# FY_-_OPTO_BOARD_2_MISC.net
KiCad netlist of a schematic drawn in EAGLE
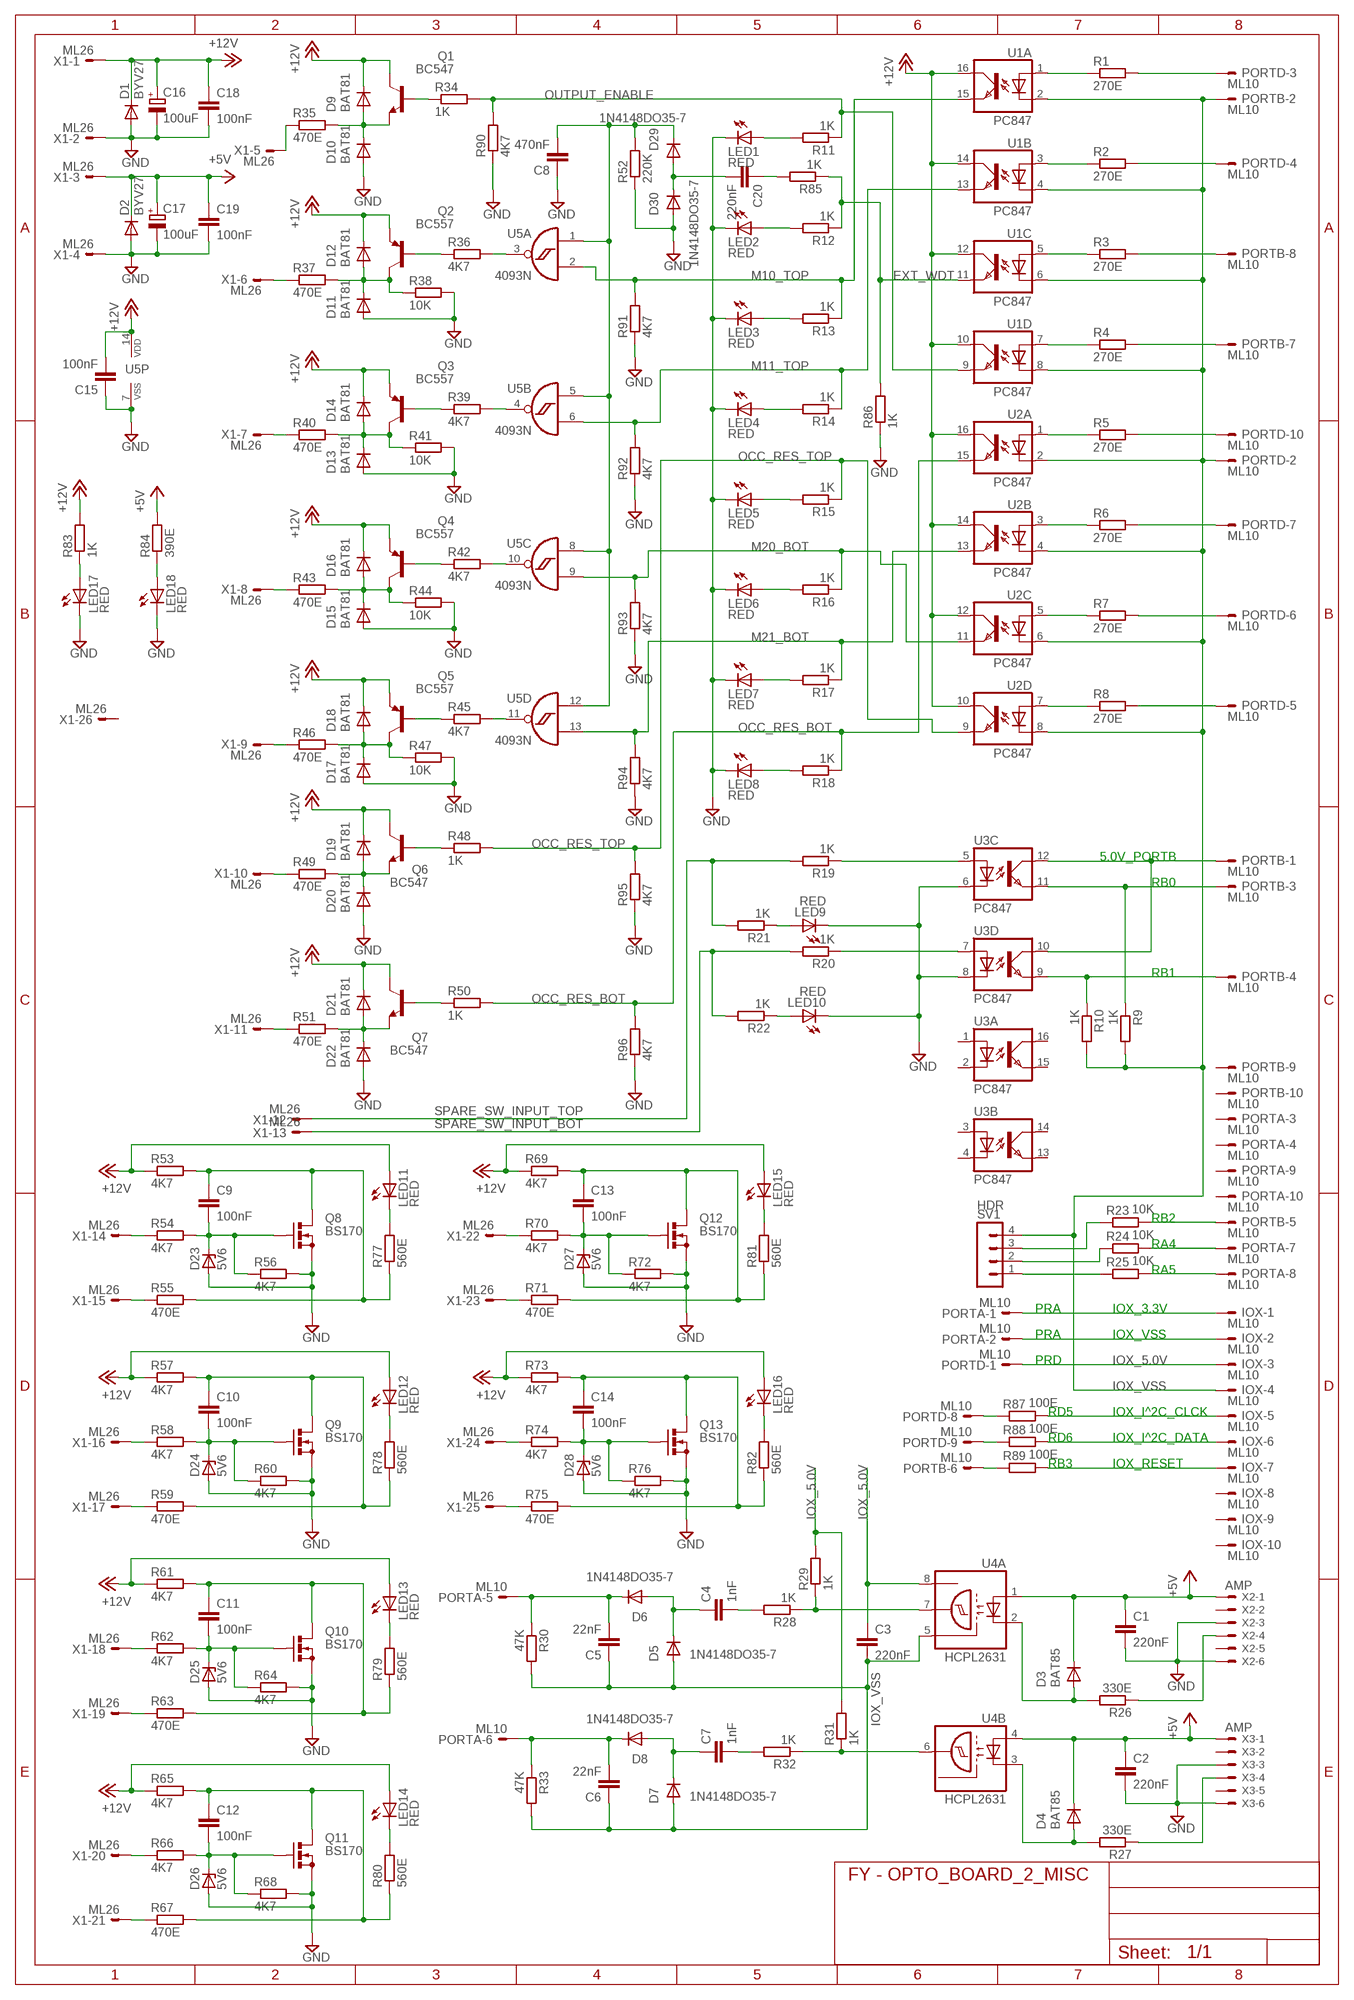
[diagram p0: schematic, sheet 1]

(export (version "E")
  (design (tool "Eeschema 10.0.6"))
  (components
    (comp (ref "C1")
      (value "220nF")
      (footprint "eagle-import:C050-025X075")
      (libsource (lib "eagle-import") (part "C-EU050-025X075"))
    )
    (comp (ref "C2")
      (value "220nF")
      (footprint "eagle-import:C050-025X075")
      (libsource (lib "eagle-import") (part "C-EU050-025X075"))
    )
    (comp (ref "C3")
      (value "220nF")
      (footprint "eagle-import:C050-025X075")
      (libsource (lib "eagle-import") (part "C-EU050-025X075"))
    )
    (comp (ref "C4")
      (value "1nF")
      (footprint "eagle-import:C050-025X075")
      (libsource (lib "eagle-import") (part "C-EU050-025X075"))
    )
    (comp (ref "C5")
      (value "22nF")
      (footprint "eagle-import:C050-025X075")
      (libsource (lib "eagle-import") (part "C-EU050-025X075"))
    )
    (comp (ref "C6")
      (value "22nF")
      (footprint "eagle-import:C050-025X075")
      (libsource (lib "eagle-import") (part "C-EU050-025X075"))
    )
    (comp (ref "C7")
      (value "1nF")
      (footprint "eagle-import:C050-025X075")
      (libsource (lib "eagle-import") (part "C-EU050-025X075"))
    )
    (comp (ref "C8")
      (value "470nF")
      (footprint "eagle-import:C050-025X075")
      (libsource (lib "eagle-import") (part "C-EU050-025X075"))
    )
    (comp (ref "C9")
      (value "100nF")
      (footprint "eagle-import:C050-025X075")
      (libsource (lib "eagle-import") (part "C-EU050-025X075"))
    )
    (comp (ref "C10")
      (value "100nF")
      (footprint "eagle-import:C050-025X075")
      (libsource (lib "eagle-import") (part "C-EU050-025X075"))
    )
    (comp (ref "C11")
      (value "100nF")
      (footprint "eagle-import:C050-025X075")
      (libsource (lib "eagle-import") (part "C-EU050-025X075"))
    )
    (comp (ref "C12")
      (value "100nF")
      (footprint "eagle-import:C050-025X075")
      (libsource (lib "eagle-import") (part "C-EU050-025X075"))
    )
    (comp (ref "C13")
      (value "100nF")
      (footprint "eagle-import:C050-025X075")
      (libsource (lib "eagle-import") (part "C-EU050-025X075"))
    )
    (comp (ref "C14")
      (value "100nF")
      (footprint "eagle-import:C050-025X075")
      (libsource (lib "eagle-import") (part "C-EU050-025X075"))
    )
    (comp (ref "C15")
      (value "100nF")
      (footprint "eagle-import:C050-025X075")
      (libsource (lib "eagle-import") (part "C-EU050-025X075"))
    )
    (comp (ref "C16")
      (value "100uF")
      (footprint "eagle-import:E5-8,5")
      (libsource (lib "eagle-import") (part "CPOL-EUE5-8.5"))
    )
    (comp (ref "C17")
      (value "100uF")
      (footprint "eagle-import:E5-8,5")
      (libsource (lib "eagle-import") (part "CPOL-EUE5-8.5"))
    )
    (comp (ref "C18")
      (value "100nF")
      (footprint "eagle-import:C050-025X075")
      (libsource (lib "eagle-import") (part "C-EU050-025X075"))
    )
    (comp (ref "C19")
      (value "100nF")
      (footprint "eagle-import:C050-025X075")
      (libsource (lib "eagle-import") (part "C-EU050-025X075"))
    )
    (comp (ref "C20")
      (value "220nF")
      (footprint "eagle-import:C050-025X075")
      (libsource (lib "eagle-import") (part "C-EU050-025X075"))
    )
    (comp (ref "D1")
      (value "BYV27")
      (footprint "eagle-import:SOD57-10")
      (libsource (lib "eagle-import") (part "BYV27"))
    )
    (comp (ref "D2")
      (value "BYV27")
      (footprint "eagle-import:SOD57-10")
      (libsource (lib "eagle-import") (part "BYV27"))
    )
    (comp (ref "D3")
      (value "BAT85")
      (footprint "eagle-import:DO34-7")
      (libsource (lib "eagle-import") (part "BAT81"))
    )
    (comp (ref "D4")
      (value "BAT85")
      (footprint "eagle-import:DO34-7")
      (libsource (lib "eagle-import") (part "BAT81"))
    )
    (comp (ref "D5")
      (value "1N4148DO35-7")
      (footprint "eagle-import:DO35-7")
      (libsource (lib "eagle-import") (part "1N4148DO35-7"))
    )
    (comp (ref "D6")
      (value "1N4148DO35-7")
      (footprint "eagle-import:DO35-7")
      (libsource (lib "eagle-import") (part "1N4148DO35-7"))
    )
    (comp (ref "D7")
      (value "1N4148DO35-7")
      (footprint "eagle-import:DO35-7")
      (libsource (lib "eagle-import") (part "1N4148DO35-7"))
    )
    (comp (ref "D8")
      (value "1N4148DO35-7")
      (footprint "eagle-import:DO35-7")
      (libsource (lib "eagle-import") (part "1N4148DO35-7"))
    )
    (comp (ref "D9")
      (value "BAT81")
      (footprint "eagle-import:DO34-7")
      (libsource (lib "eagle-import") (part "BAT81"))
    )
    (comp (ref "D10")
      (value "BAT81")
      (footprint "eagle-import:DO34-7")
      (libsource (lib "eagle-import") (part "BAT81"))
    )
    (comp (ref "D11")
      (value "BAT81")
      (footprint "eagle-import:DO34-7")
      (libsource (lib "eagle-import") (part "BAT81"))
    )
    (comp (ref "D12")
      (value "BAT81")
      (footprint "eagle-import:DO34-7")
      (libsource (lib "eagle-import") (part "BAT81"))
    )
    (comp (ref "D13")
      (value "BAT81")
      (footprint "eagle-import:DO34-7")
      (libsource (lib "eagle-import") (part "BAT81"))
    )
    (comp (ref "D14")
      (value "BAT81")
      (footprint "eagle-import:DO34-7")
      (libsource (lib "eagle-import") (part "BAT81"))
    )
    (comp (ref "D15")
      (value "BAT81")
      (footprint "eagle-import:DO34-7")
      (libsource (lib "eagle-import") (part "BAT81"))
    )
    (comp (ref "D16")
      (value "BAT81")
      (footprint "eagle-import:DO34-7")
      (libsource (lib "eagle-import") (part "BAT81"))
    )
    (comp (ref "D17")
      (value "BAT81")
      (footprint "eagle-import:DO34-7")
      (libsource (lib "eagle-import") (part "BAT81"))
    )
    (comp (ref "D18")
      (value "BAT81")
      (footprint "eagle-import:DO34-7")
      (libsource (lib "eagle-import") (part "BAT81"))
    )
    (comp (ref "D19")
      (value "BAT81")
      (footprint "eagle-import:DO34-7")
      (libsource (lib "eagle-import") (part "BAT81"))
    )
    (comp (ref "D20")
      (value "BAT81")
      (footprint "eagle-import:DO34-7")
      (libsource (lib "eagle-import") (part "BAT81"))
    )
    (comp (ref "D21")
      (value "BAT81")
      (footprint "eagle-import:DO34-7")
      (libsource (lib "eagle-import") (part "BAT81"))
    )
    (comp (ref "D22")
      (value "BAT81")
      (footprint "eagle-import:DO34-7")
      (libsource (lib "eagle-import") (part "BAT81"))
    )
    (comp (ref "D23")
      (value "5V6")
      (footprint "eagle-import:DO34Z7")
      (libsource (lib "eagle-import") (part "ZENER-DIODEDO34-7"))
    )
    (comp (ref "D24")
      (value "5V6")
      (footprint "eagle-import:DO34Z7")
      (libsource (lib "eagle-import") (part "ZENER-DIODEDO34-7"))
    )
    (comp (ref "D25")
      (value "5V6")
      (footprint "eagle-import:DO34Z7")
      (libsource (lib "eagle-import") (part "ZENER-DIODEDO34-7"))
    )
    (comp (ref "D26")
      (value "5V6")
      (footprint "eagle-import:DO34Z7")
      (libsource (lib "eagle-import") (part "ZENER-DIODEDO34-7"))
    )
    (comp (ref "D27")
      (value "5V6")
      (footprint "eagle-import:DO34Z7")
      (libsource (lib "eagle-import") (part "ZENER-DIODEDO34-7"))
    )
    (comp (ref "D28")
      (value "5V6")
      (footprint "eagle-import:DO34Z7")
      (libsource (lib "eagle-import") (part "ZENER-DIODEDO34-7"))
    )
    (comp (ref "D29")
      (value "1N4148DO35-7")
      (footprint "eagle-import:DO35-7")
      (libsource (lib "eagle-import") (part "1N4148DO35-7"))
    )
    (comp (ref "D30")
      (value "1N4148DO35-7")
      (footprint "eagle-import:DO35-7")
      (libsource (lib "eagle-import") (part "1N4148DO35-7"))
    )
    (comp (ref "IOX")
      (value "ML10")
      (footprint "eagle-import:ML10")
      (libsource (lib "eagle-import") (part "ML10?E"))
    )
    (comp (ref "LED1")
      (value "RED")
      (footprint "eagle-import:LED3MM")
      (libsource (lib "eagle-import") (part "LED3MM"))
    )
    (comp (ref "LED2")
      (value "RED")
      (footprint "eagle-import:LED3MM")
      (libsource (lib "eagle-import") (part "LED3MM"))
    )
    (comp (ref "LED3")
      (value "RED")
      (footprint "eagle-import:LED3MM")
      (libsource (lib "eagle-import") (part "LED3MM"))
    )
    (comp (ref "LED4")
      (value "RED")
      (footprint "eagle-import:LED3MM")
      (libsource (lib "eagle-import") (part "LED3MM"))
    )
    (comp (ref "LED5")
      (value "RED")
      (footprint "eagle-import:LED3MM")
      (libsource (lib "eagle-import") (part "LED3MM"))
    )
    (comp (ref "LED6")
      (value "RED")
      (footprint "eagle-import:LED3MM")
      (libsource (lib "eagle-import") (part "LED3MM"))
    )
    (comp (ref "LED7")
      (value "RED")
      (footprint "eagle-import:LED3MM")
      (libsource (lib "eagle-import") (part "LED3MM"))
    )
    (comp (ref "LED8")
      (value "RED")
      (footprint "eagle-import:LED3MM")
      (libsource (lib "eagle-import") (part "LED3MM"))
    )
    (comp (ref "LED9")
      (value "RED")
      (footprint "eagle-import:LED3MM")
      (libsource (lib "eagle-import") (part "LED3MM"))
    )
    (comp (ref "LED10")
      (value "RED")
      (footprint "eagle-import:LED3MM")
      (libsource (lib "eagle-import") (part "LED3MM"))
    )
    (comp (ref "LED11")
      (value "RED")
      (footprint "eagle-import:LED3MM")
      (libsource (lib "eagle-import") (part "LED3MM"))
    )
    (comp (ref "LED12")
      (value "RED")
      (footprint "eagle-import:LED3MM")
      (libsource (lib "eagle-import") (part "LED3MM"))
    )
    (comp (ref "LED13")
      (value "RED")
      (footprint "eagle-import:LED3MM")
      (libsource (lib "eagle-import") (part "LED3MM"))
    )
    (comp (ref "LED14")
      (value "RED")
      (footprint "eagle-import:LED3MM")
      (libsource (lib "eagle-import") (part "LED3MM"))
    )
    (comp (ref "LED15")
      (value "RED")
      (footprint "eagle-import:LED3MM")
      (libsource (lib "eagle-import") (part "LED3MM"))
    )
    (comp (ref "LED16")
      (value "RED")
      (footprint "eagle-import:LED3MM")
      (libsource (lib "eagle-import") (part "LED3MM"))
    )
    (comp (ref "LED17")
      (value "RED")
      (footprint "eagle-import:LED3MM")
      (libsource (lib "eagle-import") (part "LED3MM"))
    )
    (comp (ref "LED18")
      (value "RED")
      (footprint "eagle-import:LED3MM")
      (libsource (lib "eagle-import") (part "LED3MM"))
    )
    (comp (ref "PORTA")
      (value "ML10")
      (footprint "eagle-import:ML10")
      (libsource (lib "eagle-import") (part "ML10?E"))
    )
    (comp (ref "PORTB")
      (value "ML10")
      (footprint "eagle-import:ML10")
      (libsource (lib "eagle-import") (part "ML10?E"))
    )
    (comp (ref "PORTD")
      (value "ML10")
      (footprint "eagle-import:ML10")
      (libsource (lib "eagle-import") (part "ML10?E"))
    )
    (comp (ref "Q1")
      (value "BC547")
      (footprint "eagle-import:TO92")
      (libsource (lib "eagle-import") (part "BC547"))
    )
    (comp (ref "Q2")
      (value "BC557")
      (footprint "eagle-import:TO92")
      (libsource (lib "eagle-import") (part "BC557"))
    )
    (comp (ref "Q3")
      (value "BC557")
      (footprint "eagle-import:TO92")
      (libsource (lib "eagle-import") (part "BC557"))
    )
    (comp (ref "Q4")
      (value "BC557")
      (footprint "eagle-import:TO92")
      (libsource (lib "eagle-import") (part "BC557"))
    )
    (comp (ref "Q5")
      (value "BC557")
      (footprint "eagle-import:TO92")
      (libsource (lib "eagle-import") (part "BC557"))
    )
    (comp (ref "Q6")
      (value "BC547")
      (footprint "eagle-import:TO92")
      (libsource (lib "eagle-import") (part "BC547"))
    )
    (comp (ref "Q7")
      (value "BC547")
      (footprint "eagle-import:TO92")
      (libsource (lib "eagle-import") (part "BC547"))
    )
    (comp (ref "Q8")
      (value "BS170")
      (footprint "eagle-import:SOT54E")
      (libsource (lib "eagle-import") (part "BS170"))
    )
    (comp (ref "Q9")
      (value "BS170")
      (footprint "eagle-import:SOT54E")
      (libsource (lib "eagle-import") (part "BS170"))
    )
    (comp (ref "Q10")
      (value "BS170")
      (footprint "eagle-import:SOT54E")
      (libsource (lib "eagle-import") (part "BS170"))
    )
    (comp (ref "Q11")
      (value "BS170")
      (footprint "eagle-import:SOT54E")
      (libsource (lib "eagle-import") (part "BS170"))
    )
    (comp (ref "Q12")
      (value "BS170")
      (footprint "eagle-import:SOT54E")
      (libsource (lib "eagle-import") (part "BS170"))
    )
    (comp (ref "Q13")
      (value "BS170")
      (footprint "eagle-import:SOT54E")
      (libsource (lib "eagle-import") (part "BS170"))
    )
    (comp (ref "R1")
      (value "270E")
      (footprint "eagle-import:0207_10")
      (libsource (lib "eagle-import") (part "R-EU_0207/10"))
    )
    (comp (ref "R2")
      (value "270E")
      (footprint "eagle-import:0207_10")
      (libsource (lib "eagle-import") (part "R-EU_0207/10"))
    )
    (comp (ref "R3")
      (value "270E")
      (footprint "eagle-import:0207_10")
      (libsource (lib "eagle-import") (part "R-EU_0207/10"))
    )
    (comp (ref "R4")
      (value "270E")
      (footprint "eagle-import:0207_10")
      (libsource (lib "eagle-import") (part "R-EU_0207/10"))
    )
    (comp (ref "R5")
      (value "270E")
      (footprint "eagle-import:0207_10")
      (libsource (lib "eagle-import") (part "R-EU_0207/10"))
    )
    (comp (ref "R6")
      (value "270E")
      (footprint "eagle-import:0207_10")
      (libsource (lib "eagle-import") (part "R-EU_0207/10"))
    )
    (comp (ref "R7")
      (value "270E")
      (footprint "eagle-import:0207_10")
      (libsource (lib "eagle-import") (part "R-EU_0207/10"))
    )
    (comp (ref "R8")
      (value "270E")
      (footprint "eagle-import:0207_10")
      (libsource (lib "eagle-import") (part "R-EU_0207/10"))
    )
    (comp (ref "R9")
      (value "1K")
      (footprint "eagle-import:0207_10")
      (libsource (lib "eagle-import") (part "R-EU_0207/10"))
    )
    (comp (ref "R10")
      (value "1K")
      (footprint "eagle-import:0207_10")
      (libsource (lib "eagle-import") (part "R-EU_0207/10"))
    )
    (comp (ref "R11")
      (value "1K")
      (footprint "eagle-import:0207_10")
      (libsource (lib "eagle-import") (part "R-EU_0207/10"))
    )
    (comp (ref "R12")
      (value "1K")
      (footprint "eagle-import:0207_10")
      (libsource (lib "eagle-import") (part "R-EU_0207/10"))
    )
    (comp (ref "R13")
      (value "1K")
      (footprint "eagle-import:0207_10")
      (libsource (lib "eagle-import") (part "R-EU_0207/10"))
    )
    (comp (ref "R14")
      (value "1K")
      (footprint "eagle-import:0207_10")
      (libsource (lib "eagle-import") (part "R-EU_0207/10"))
    )
    (comp (ref "R15")
      (value "1K")
      (footprint "eagle-import:0207_10")
      (libsource (lib "eagle-import") (part "R-EU_0207/10"))
    )
    (comp (ref "R16")
      (value "1K")
      (footprint "eagle-import:0207_10")
      (libsource (lib "eagle-import") (part "R-EU_0207/10"))
    )
    (comp (ref "R17")
      (value "1K")
      (footprint "eagle-import:0207_10")
      (libsource (lib "eagle-import") (part "R-EU_0207/10"))
    )
    (comp (ref "R18")
      (value "1K")
      (footprint "eagle-import:0207_10")
      (libsource (lib "eagle-import") (part "R-EU_0207/10"))
    )
    (comp (ref "R19")
      (value "1K")
      (footprint "eagle-import:0207_10")
      (libsource (lib "eagle-import") (part "R-EU_0207/10"))
    )
    (comp (ref "R20")
      (value "1K")
      (footprint "eagle-import:0207_10")
      (libsource (lib "eagle-import") (part "R-EU_0207/10"))
    )
    (comp (ref "R21")
      (value "1K")
      (footprint "eagle-import:0207_10")
      (libsource (lib "eagle-import") (part "R-EU_0207/10"))
    )
    (comp (ref "R22")
      (value "1K")
      (footprint "eagle-import:0207_10")
      (libsource (lib "eagle-import") (part "R-EU_0207/10"))
    )
    (comp (ref "R23")
      (value "10K")
      (footprint "eagle-import:0207_10")
      (libsource (lib "eagle-import") (part "R-EU_0207/10"))
    )
    (comp (ref "R24")
      (value "10K")
      (footprint "eagle-import:0207_10")
      (libsource (lib "eagle-import") (part "R-EU_0207/10"))
    )
    (comp (ref "R25")
      (value "10K")
      (footprint "eagle-import:0207_10")
      (libsource (lib "eagle-import") (part "R-EU_0207/10"))
    )
    (comp (ref "R26")
      (value "330E")
      (footprint "eagle-import:0207_10")
      (libsource (lib "eagle-import") (part "R-EU_0207/10"))
    )
    (comp (ref "R27")
      (value "330E")
      (footprint "eagle-import:0207_10")
      (libsource (lib "eagle-import") (part "R-EU_0207/10"))
    )
    (comp (ref "R28")
      (value "1K")
      (footprint "eagle-import:0207_10")
      (libsource (lib "eagle-import") (part "R-EU_0207/10"))
    )
    (comp (ref "R29")
      (value "1K")
      (footprint "eagle-import:0207_10")
      (libsource (lib "eagle-import") (part "R-EU_0207/10"))
    )
    (comp (ref "R30")
      (value "47K")
      (footprint "eagle-import:0207_10")
      (libsource (lib "eagle-import") (part "R-EU_0207/10"))
    )
    (comp (ref "R31")
      (value "1K")
      (footprint "eagle-import:0207_10")
      (libsource (lib "eagle-import") (part "R-EU_0207/10"))
    )
    (comp (ref "R32")
      (value "1K")
      (footprint "eagle-import:0207_10")
      (libsource (lib "eagle-import") (part "R-EU_0207/10"))
    )
    (comp (ref "R33")
      (value "47K")
      (footprint "eagle-import:0207_10")
      (libsource (lib "eagle-import") (part "R-EU_0207/10"))
    )
    (comp (ref "R34")
      (value "1K")
      (footprint "eagle-import:0207_10")
      (libsource (lib "eagle-import") (part "R-EU_0207/10"))
    )
    (comp (ref "R35")
      (value "470E")
      (footprint "eagle-import:0207_10")
      (libsource (lib "eagle-import") (part "R-EU_0207/10"))
    )
    (comp (ref "R36")
      (value "4K7")
      (footprint "eagle-import:0207_10")
      (libsource (lib "eagle-import") (part "R-EU_0207/10"))
    )
    (comp (ref "R37")
      (value "470E")
      (footprint "eagle-import:0207_10")
      (libsource (lib "eagle-import") (part "R-EU_0207/10"))
    )
    (comp (ref "R38")
      (value "10K")
      (footprint "eagle-import:0207_10")
      (libsource (lib "eagle-import") (part "R-EU_0207/10"))
    )
    (comp (ref "R39")
      (value "4K7")
      (footprint "eagle-import:0207_10")
      (libsource (lib "eagle-import") (part "R-EU_0207/10"))
    )
    (comp (ref "R40")
      (value "470E")
      (footprint "eagle-import:0207_10")
      (libsource (lib "eagle-import") (part "R-EU_0207/10"))
    )
    (comp (ref "R41")
      (value "10K")
      (footprint "eagle-import:0207_10")
      (libsource (lib "eagle-import") (part "R-EU_0207/10"))
    )
    (comp (ref "R42")
      (value "4K7")
      (footprint "eagle-import:0207_10")
      (libsource (lib "eagle-import") (part "R-EU_0207/10"))
    )
    (comp (ref "R43")
      (value "470E")
      (footprint "eagle-import:0207_10")
      (libsource (lib "eagle-import") (part "R-EU_0207/10"))
    )
    (comp (ref "R44")
      (value "10K")
      (footprint "eagle-import:0207_10")
      (libsource (lib "eagle-import") (part "R-EU_0207/10"))
    )
    (comp (ref "R45")
      (value "4K7")
      (footprint "eagle-import:0207_10")
      (libsource (lib "eagle-import") (part "R-EU_0207/10"))
    )
    (comp (ref "R46")
      (value "470E")
      (footprint "eagle-import:0207_10")
      (libsource (lib "eagle-import") (part "R-EU_0207/10"))
    )
    (comp (ref "R47")
      (value "10K")
      (footprint "eagle-import:0207_10")
      (libsource (lib "eagle-import") (part "R-EU_0207/10"))
    )
    (comp (ref "R48")
      (value "1K")
      (footprint "eagle-import:0207_10")
      (libsource (lib "eagle-import") (part "R-EU_0207/10"))
    )
    (comp (ref "R49")
      (value "470E")
      (footprint "eagle-import:0207_10")
      (libsource (lib "eagle-import") (part "R-EU_0207/10"))
    )
    (comp (ref "R50")
      (value "1K")
      (footprint "eagle-import:0207_10")
      (libsource (lib "eagle-import") (part "R-EU_0207/10"))
    )
    (comp (ref "R51")
      (value "470E")
      (footprint "eagle-import:0207_10")
      (libsource (lib "eagle-import") (part "R-EU_0207/10"))
    )
    (comp (ref "R52")
      (value "220K")
      (footprint "eagle-import:0207_10")
      (libsource (lib "eagle-import") (part "R-EU_0207/10"))
    )
    (comp (ref "R53")
      (value "4K7")
      (footprint "eagle-import:0207_10")
      (libsource (lib "eagle-import") (part "R-EU_0207/10"))
    )
    (comp (ref "R54")
      (value "4K7")
      (footprint "eagle-import:0207_10")
      (libsource (lib "eagle-import") (part "R-EU_0207/10"))
    )
    (comp (ref "R55")
      (value "470E")
      (footprint "eagle-import:0207_10")
      (libsource (lib "eagle-import") (part "R-EU_0207/10"))
    )
    (comp (ref "R56")
      (value "4K7")
      (footprint "eagle-import:0207_10")
      (libsource (lib "eagle-import") (part "R-EU_0207/10"))
    )
    (comp (ref "R57")
      (value "4K7")
      (footprint "eagle-import:0207_10")
      (libsource (lib "eagle-import") (part "R-EU_0207/10"))
    )
    (comp (ref "R58")
      (value "4K7")
      (footprint "eagle-import:0207_10")
      (libsource (lib "eagle-import") (part "R-EU_0207/10"))
    )
    (comp (ref "R59")
      (value "470E")
      (footprint "eagle-import:0207_10")
      (libsource (lib "eagle-import") (part "R-EU_0207/10"))
    )
    (comp (ref "R60")
      (value "4K7")
      (footprint "eagle-import:0207_10")
      (libsource (lib "eagle-import") (part "R-EU_0207/10"))
    )
    (comp (ref "R61")
      (value "4K7")
      (footprint "eagle-import:0207_10")
      (libsource (lib "eagle-import") (part "R-EU_0207/10"))
    )
    (comp (ref "R62")
      (value "4K7")
      (footprint "eagle-import:0207_10")
      (libsource (lib "eagle-import") (part "R-EU_0207/10"))
    )
    (comp (ref "R63")
      (value "470E")
      (footprint "eagle-import:0207_10")
      (libsource (lib "eagle-import") (part "R-EU_0207/10"))
    )
    (comp (ref "R64")
      (value "4K7")
      (footprint "eagle-import:0207_10")
      (libsource (lib "eagle-import") (part "R-EU_0207/10"))
    )
    (comp (ref "R65")
      (value "4K7")
      (footprint "eagle-import:0207_10")
      (libsource (lib "eagle-import") (part "R-EU_0207/10"))
    )
    (comp (ref "R66")
      (value "4K7")
      (footprint "eagle-import:0207_10")
      (libsource (lib "eagle-import") (part "R-EU_0207/10"))
    )
    (comp (ref "R67")
      (value "470E")
      (footprint "eagle-import:0207_10")
      (libsource (lib "eagle-import") (part "R-EU_0207/10"))
    )
    (comp (ref "R68")
      (value "4K7")
      (footprint "eagle-import:0207_10")
      (libsource (lib "eagle-import") (part "R-EU_0207/10"))
    )
    (comp (ref "R69")
      (value "4K7")
      (footprint "eagle-import:0207_10")
      (libsource (lib "eagle-import") (part "R-EU_0207/10"))
    )
    (comp (ref "R70")
      (value "4K7")
      (footprint "eagle-import:0207_10")
      (libsource (lib "eagle-import") (part "R-EU_0207/10"))
    )
    (comp (ref "R71")
      (value "470E")
      (footprint "eagle-import:0207_10")
      (libsource (lib "eagle-import") (part "R-EU_0207/10"))
    )
    (comp (ref "R72")
      (value "4K7")
      (footprint "eagle-import:0207_10")
      (libsource (lib "eagle-import") (part "R-EU_0207/10"))
    )
    (comp (ref "R73")
      (value "4K7")
      (footprint "eagle-import:0207_10")
      (libsource (lib "eagle-import") (part "R-EU_0207/10"))
    )
    (comp (ref "R74")
      (value "4K7")
      (footprint "eagle-import:0207_10")
      (libsource (lib "eagle-import") (part "R-EU_0207/10"))
    )
    (comp (ref "R75")
      (value "470E")
      (footprint "eagle-import:0207_10")
      (libsource (lib "eagle-import") (part "R-EU_0207/10"))
    )
    (comp (ref "R76")
      (value "4K7")
      (footprint "eagle-import:0207_10")
      (libsource (lib "eagle-import") (part "R-EU_0207/10"))
    )
    (comp (ref "R77")
      (value "560E")
      (footprint "eagle-import:0207_10")
      (libsource (lib "eagle-import") (part "R-EU_0207/10"))
    )
    (comp (ref "R78")
      (value "560E")
      (footprint "eagle-import:0207_10")
      (libsource (lib "eagle-import") (part "R-EU_0207/10"))
    )
    (comp (ref "R79")
      (value "560E")
      (footprint "eagle-import:0207_10")
      (libsource (lib "eagle-import") (part "R-EU_0207/10"))
    )
    (comp (ref "R80")
      (value "560E")
      (footprint "eagle-import:0207_10")
      (libsource (lib "eagle-import") (part "R-EU_0207/10"))
    )
    (comp (ref "R81")
      (value "560E")
      (footprint "eagle-import:0207_10")
      (libsource (lib "eagle-import") (part "R-EU_0207/10"))
    )
    (comp (ref "R82")
      (value "560E")
      (footprint "eagle-import:0207_10")
      (libsource (lib "eagle-import") (part "R-EU_0207/10"))
    )
    (comp (ref "R83")
      (value "1K")
      (footprint "eagle-import:0207_10")
      (libsource (lib "eagle-import") (part "R-EU_0207/10"))
    )
    (comp (ref "R84")
      (value "390E")
      (footprint "eagle-import:0207_10")
      (libsource (lib "eagle-import") (part "R-EU_0207/10"))
    )
    (comp (ref "R85")
      (value "1K")
      (footprint "eagle-import:0207_10")
      (libsource (lib "eagle-import") (part "R-EU_0207/10"))
    )
    (comp (ref "R86")
      (value "1K")
      (footprint "eagle-import:0207_10")
      (libsource (lib "eagle-import") (part "R-EU_0207/10"))
    )
    (comp (ref "R87")
      (value "100E")
      (footprint "eagle-import:0207_10")
      (libsource (lib "eagle-import") (part "R-EU_0207/10"))
    )
    (comp (ref "R88")
      (value "100E")
      (footprint "eagle-import:0207_10")
      (libsource (lib "eagle-import") (part "R-EU_0207/10"))
    )
    (comp (ref "R89")
      (value "100E")
      (footprint "eagle-import:0207_10")
      (libsource (lib "eagle-import") (part "R-EU_0207/10"))
    )
    (comp (ref "R90")
      (value "4K7")
      (footprint "eagle-import:0207_10")
      (libsource (lib "eagle-import") (part "R-EU_0207/10"))
    )
    (comp (ref "R91")
      (value "4K7")
      (footprint "eagle-import:0207_10")
      (libsource (lib "eagle-import") (part "R-EU_0207/10"))
    )
    (comp (ref "R92")
      (value "4K7")
      (footprint "eagle-import:0207_10")
      (libsource (lib "eagle-import") (part "R-EU_0207/10"))
    )
    (comp (ref "R93")
      (value "4K7")
      (footprint "eagle-import:0207_10")
      (libsource (lib "eagle-import") (part "R-EU_0207/10"))
    )
    (comp (ref "R94")
      (value "4K7")
      (footprint "eagle-import:0207_10")
      (libsource (lib "eagle-import") (part "R-EU_0207/10"))
    )
    (comp (ref "R95")
      (value "4K7")
      (footprint "eagle-import:0207_10")
      (libsource (lib "eagle-import") (part "R-EU_0207/10"))
    )
    (comp (ref "R96")
      (value "4K7")
      (footprint "eagle-import:0207_10")
      (libsource (lib "eagle-import") (part "R-EU_0207/10"))
    )
    (comp (ref "SV1")
      (value "HDR")
      (footprint "eagle-import:MA04-1")
      (libsource (lib "eagle-import") (part "MA04-1"))
    )
    (comp (ref "U1")
      (value "PC847")
      (footprint "eagle-import:DIL16")
      (libsource (lib "eagle-import") (part "PC847"))
    )
    (comp (ref "U2")
      (value "PC847")
      (footprint "eagle-import:DIL16")
      (libsource (lib "eagle-import") (part "PC847"))
    )
    (comp (ref "U3")
      (value "PC847")
      (footprint "eagle-import:DIL16")
      (libsource (lib "eagle-import") (part "PC847"))
    )
    (comp (ref "U4")
      (value "HCPL2631")
      (footprint "eagle-import:DIL08")
      (fields (field (name "MF") "AGILENT TECHNOLOGIES") (field (name "MPN") "HCPL-2231-000E"))
      (libsource (lib "eagle-import") (part "HCPL2231"))
    )
    (comp (ref "U5")
      (value "4093N")
      (footprint "eagle-import:DIL14")
      (libsource (lib "eagle-import") (part "4093N"))
    )
    (comp (ref "X1")
      (value "ML26")
      (footprint "eagle-import:ML26")
      (libsource (lib "eagle-import") (part "ML26?E"))
    )
    (comp (ref "X2")
      (value "AMP")
      (footprint "eagle-import:22-23-2061")
      (fields (field (name "MF") "MOLEX") (field (name "MPN") "22-23-2061"))
      (libsource (lib "eagle-import") (part "22-23-2061"))
    )
    (comp (ref "X3")
      (value "AMP")
      (footprint "eagle-import:22-23-2061")
      (fields (field (name "MF") "MOLEX") (field (name "MPN") "22-23-2061"))
      (libsource (lib "eagle-import") (part "22-23-2061"))
    )
  )
  (nets
    (net (code "1") (name "+5V") (class "Default")
      (node (ref "C1") (pin "1") (pinfunction "1_1") (pintype "passive"))
      (node (ref "C17") (pin "+") (pinfunction "+_+") (pintype "passive"))
      (node (ref "C19") (pin "1") (pinfunction "1_1") (pintype "passive"))
      (node (ref "C2") (pin "1") (pinfunction "1_1") (pintype "passive"))
      (node (ref "D2") (pin "C") (pinfunction "C_C") (pintype "passive"))
      (node (ref "D3") (pin "C") (pinfunction "C_C") (pintype "passive"))
      (node (ref "D4") (pin "C") (pinfunction "C_C") (pintype "passive"))
      (node (ref "R84") (pin "2") (pinfunction "2_2") (pintype "passive"))
      (node (ref "U4") (pin "1") (pinfunction "A_1") (pintype "passive"))
      (node (ref "U4") (pin "4") (pinfunction "A_4") (pintype "passive"))
      (node (ref "X1") (pin "3") (pinfunction "S_3") (pintype "passive"))
      (node (ref "X2") (pin "1") (pinfunction "S_1") (pintype "passive"))
      (node (ref "X3") (pin "1") (pinfunction "S_1") (pintype "passive"))
    )
    (net (code "2") (name "+12V") (class "Default")
      (node (ref "C15") (pin "2") (pinfunction "2_2") (pintype "passive"))
      (node (ref "C16") (pin "+") (pinfunction "+_+") (pintype "passive"))
      (node (ref "C18") (pin "1") (pinfunction "1_1") (pintype "passive"))
      (node (ref "D1") (pin "C") (pinfunction "C_C") (pintype "passive"))
      (node (ref "D12") (pin "C") (pinfunction "C_C") (pintype "passive"))
      (node (ref "D14") (pin "C") (pinfunction "C_C") (pintype "passive"))
      (node (ref "D16") (pin "C") (pinfunction "C_C") (pintype "passive"))
      (node (ref "D18") (pin "C") (pinfunction "C_C") (pintype "passive"))
      (node (ref "D19") (pin "C") (pinfunction "C_C") (pintype "passive"))
      (node (ref "D21") (pin "C") (pinfunction "C_C") (pintype "passive"))
      (node (ref "D9") (pin "C") (pinfunction "C_C") (pintype "passive"))
      (node (ref "LED11") (pin "A") (pinfunction "A_A") (pintype "passive"))
      (node (ref "LED12") (pin "A") (pinfunction "A_A") (pintype "passive"))
      (node (ref "LED13") (pin "A") (pinfunction "A_A") (pintype "passive"))
      (node (ref "LED14") (pin "A") (pinfunction "A_A") (pintype "passive"))
      (node (ref "LED15") (pin "A") (pinfunction "A_A") (pintype "passive"))
      (node (ref "LED16") (pin "A") (pinfunction "A_A") (pintype "passive"))
      (node (ref "Q1") (pin "3") (pinfunction "C_3") (pintype "passive"))
      (node (ref "Q2") (pin "1") (pinfunction "E_1") (pintype "passive"))
      (node (ref "Q3") (pin "1") (pinfunction "E_1") (pintype "passive"))
      (node (ref "Q4") (pin "1") (pinfunction "E_1") (pintype "passive"))
      (node (ref "Q5") (pin "1") (pinfunction "E_1") (pintype "passive"))
      (node (ref "Q6") (pin "3") (pinfunction "C_3") (pintype "passive"))
      (node (ref "Q7") (pin "3") (pinfunction "C_3") (pintype "passive"))
      (node (ref "R53") (pin "1") (pinfunction "1_1") (pintype "passive"))
      (node (ref "R57") (pin "1") (pinfunction "1_1") (pintype "passive"))
      (node (ref "R61") (pin "1") (pinfunction "1_1") (pintype "passive"))
      (node (ref "R65") (pin "1") (pinfunction "1_1") (pintype "passive"))
      (node (ref "R69") (pin "1") (pinfunction "1_1") (pintype "passive"))
      (node (ref "R73") (pin "1") (pinfunction "1_1") (pintype "passive"))
      (node (ref "R83") (pin "2") (pinfunction "2_2") (pintype "passive"))
      (node (ref "U1") (pin "10") (pinfunction "COL_10") (pintype "passive"))
      (node (ref "U1") (pin "12") (pinfunction "COL_12") (pintype "passive"))
      (node (ref "U1") (pin "14") (pinfunction "COL_14") (pintype "passive"))
      (node (ref "U1") (pin "16") (pinfunction "COL_16") (pintype "passive"))
      (node (ref "U2") (pin "10") (pinfunction "COL_10") (pintype "passive"))
      (node (ref "U2") (pin "12") (pinfunction "COL_12") (pintype "passive"))
      (node (ref "U2") (pin "14") (pinfunction "COL_14") (pintype "passive"))
      (node (ref "U2") (pin "16") (pinfunction "COL_16") (pintype "passive"))
      (node (ref "U5") (pin "14") (pinfunction "VDD_14") (pintype "power_in"))
      (node (ref "X1") (pin "1") (pinfunction "S_1") (pintype "passive"))
    )
    (net (code "3") (name "/EXT_WDT") (class "Default")
      (node (ref "R12") (pin "1") (pinfunction "1_1") (pintype "passive"))
      (node (ref "R85") (pin "1") (pinfunction "1_1") (pintype "passive"))
      (node (ref "R86") (pin "2") (pinfunction "2_2") (pintype "passive"))
      (node (ref "U1") (pin "11") (pinfunction "EMIT_11") (pintype "passive"))
    )
    (net (code "4") (name "/IOX_5.0V") (class "Default")
      (node (ref "C3") (pin "1") (pinfunction "1_1") (pintype "passive"))
      (node (ref "IOX") (pin "3") (pinfunction "S_3") (pintype "passive"))
      (node (ref "PORTD") (pin "1") (pinfunction "S_1") (pintype "passive"))
      (node (ref "R29") (pin "2") (pinfunction "2_2") (pintype "passive"))
      (node (ref "R31") (pin "2") (pinfunction "2_2") (pintype "passive"))
      (node (ref "U4") (pin "8") (pinfunction "VCC_8") (pintype "passive"))
    )
    (net (code "5") (name "/IOX_VSS") (class "Default")
      (node (ref "C3") (pin "2") (pinfunction "2_2") (pintype "passive"))
      (node (ref "C5") (pin "1") (pinfunction "1_1") (pintype "passive"))
      (node (ref "C6") (pin "1") (pinfunction "1_1") (pintype "passive"))
      (node (ref "D5") (pin "A") (pinfunction "A_A") (pintype "passive"))
      (node (ref "D7") (pin "A") (pinfunction "A_A") (pintype "passive"))
      (node (ref "IOX") (pin "4") (pinfunction "S_4") (pintype "passive"))
      (node (ref "PORTB") (pin "2") (pinfunction "S_2") (pintype "passive"))
      (node (ref "PORTD") (pin "2") (pinfunction "S_2") (pintype "passive"))
      (node (ref "R10") (pin "2") (pinfunction "2_2") (pintype "passive"))
      (node (ref "R30") (pin "2") (pinfunction "2_2") (pintype "passive"))
      (node (ref "R33") (pin "2") (pinfunction "2_2") (pintype "passive"))
      (node (ref "R9") (pin "2") (pinfunction "2_2") (pintype "passive"))
      (node (ref "SV1") (pin "4") (pinfunction "4_4") (pintype "passive"))
      (node (ref "U1") (pin "2") (pinfunction "C_2") (pintype "passive"))
      (node (ref "U1") (pin "4") (pinfunction "C_4") (pintype "passive"))
      (node (ref "U1") (pin "6") (pinfunction "C_6") (pintype "passive"))
      (node (ref "U1") (pin "8") (pinfunction "C_8") (pintype "passive"))
      (node (ref "U2") (pin "2") (pinfunction "C_2") (pintype "passive"))
      (node (ref "U2") (pin "4") (pinfunction "C_4") (pintype "passive"))
      (node (ref "U2") (pin "6") (pinfunction "C_6") (pintype "passive"))
      (node (ref "U2") (pin "8") (pinfunction "C_8") (pintype "passive"))
      (node (ref "U4") (pin "5") (pinfunction "GND_5") (pintype "passive"))
    )
    (net (code "6") (name "/M10_TOP") (class "Default")
      (node (ref "R13") (pin "1") (pinfunction "1_1") (pintype "passive"))
      (node (ref "R91") (pin "2") (pinfunction "2_2") (pintype "passive"))
      (node (ref "U1") (pin "15") (pinfunction "EMIT_15") (pintype "passive"))
      (node (ref "U5") (pin "2") (pinfunction "I1_2") (pintype "input"))
    )
    (net (code "7") (name "/M11_TOP") (class "Default")
      (node (ref "R14") (pin "1") (pinfunction "1_1") (pintype "passive"))
      (node (ref "R92") (pin "2") (pinfunction "2_2") (pintype "passive"))
      (node (ref "U1") (pin "13") (pinfunction "EMIT_13") (pintype "passive"))
      (node (ref "U5") (pin "6") (pinfunction "I1_6") (pintype "input"))
    )
    (net (code "8") (name "/M20_BOT") (class "Default")
      (node (ref "R16") (pin "1") (pinfunction "1_1") (pintype "passive"))
      (node (ref "R93") (pin "2") (pinfunction "2_2") (pintype "passive"))
      (node (ref "U2") (pin "11") (pinfunction "EMIT_11") (pintype "passive"))
      (node (ref "U5") (pin "9") (pinfunction "I1_9") (pintype "input"))
    )
    (net (code "9") (name "/M21_BOT") (class "Default")
      (node (ref "R17") (pin "1") (pinfunction "1_1") (pintype "passive"))
      (node (ref "R94") (pin "2") (pinfunction "2_2") (pintype "passive"))
      (node (ref "U2") (pin "13") (pinfunction "EMIT_13") (pintype "passive"))
      (node (ref "U5") (pin "13") (pinfunction "I1_13") (pintype "input"))
    )
    (net (code "10") (name "/OCC_RES_BOT") (class "Default")
      (node (ref "R18") (pin "1") (pinfunction "1_1") (pintype "passive"))
      (node (ref "R50") (pin "2") (pinfunction "2_2") (pintype "passive"))
      (node (ref "R96") (pin "2") (pinfunction "2_2") (pintype "passive"))
      (node (ref "U2") (pin "15") (pinfunction "EMIT_15") (pintype "passive"))
    )
    (net (code "11") (name "/OCC_RES_TOP") (class "Default")
      (node (ref "R15") (pin "1") (pinfunction "1_1") (pintype "passive"))
      (node (ref "R48") (pin "2") (pinfunction "2_2") (pintype "passive"))
      (node (ref "R95") (pin "2") (pinfunction "2_2") (pintype "passive"))
      (node (ref "U2") (pin "9") (pinfunction "EMIT_9") (pintype "passive"))
    )
    (net (code "12") (name "/OUTPUT_ENABLE") (class "Default")
      (node (ref "R11") (pin "1") (pinfunction "1_1") (pintype "passive"))
      (node (ref "R34") (pin "2") (pinfunction "2_2") (pintype "passive"))
      (node (ref "R90") (pin "2") (pinfunction "2_2") (pintype "passive"))
      (node (ref "U1") (pin "9") (pinfunction "EMIT_9") (pintype "passive"))
    )
    (net (code "13") (name "/SPARE_SW_INPUT_BOT") (class "Default")
      (node (ref "R20") (pin "2") (pinfunction "2_2") (pintype "passive"))
      (node (ref "R22") (pin "2") (pinfunction "2_2") (pintype "passive"))
      (node (ref "X1") (pin "13") (pinfunction "S_13") (pintype "passive"))
    )
    (net (code "14") (name "/SPARE_SW_INPUT_TOP") (class "Default")
      (node (ref "R19") (pin "2") (pinfunction "2_2") (pintype "passive"))
      (node (ref "R21") (pin "2") (pinfunction "2_2") (pintype "passive"))
      (node (ref "X1") (pin "12") (pinfunction "S_12") (pintype "passive"))
    )
    (net (code "15") (name "GND") (class "Default")
      (node (ref "C1") (pin "2") (pinfunction "2_2") (pintype "passive"))
      (node (ref "C15") (pin "1") (pinfunction "1_1") (pintype "passive"))
      (node (ref "C16") (pin "-") (pinfunction "-_-") (pintype "passive"))
      (node (ref "C17") (pin "-") (pinfunction "-_-") (pintype "passive"))
      (node (ref "C18") (pin "2") (pinfunction "2_2") (pintype "passive"))
      (node (ref "C19") (pin "2") (pinfunction "2_2") (pintype "passive"))
      (node (ref "C2") (pin "2") (pinfunction "2_2") (pintype "passive"))
      (node (ref "C8") (pin "1") (pinfunction "1_1") (pintype "passive"))
      (node (ref "D1") (pin "A") (pinfunction "A_A") (pintype "passive"))
      (node (ref "D10") (pin "A") (pinfunction "A_A") (pintype "passive"))
      (node (ref "D11") (pin "A") (pinfunction "A_A") (pintype "passive"))
      (node (ref "D13") (pin "A") (pinfunction "A_A") (pintype "passive"))
      (node (ref "D15") (pin "A") (pinfunction "A_A") (pintype "passive"))
      (node (ref "D17") (pin "A") (pinfunction "A_A") (pintype "passive"))
      (node (ref "D2") (pin "A") (pinfunction "A_A") (pintype "passive"))
      (node (ref "D20") (pin "A") (pinfunction "A_A") (pintype "passive"))
      (node (ref "D22") (pin "A") (pinfunction "A_A") (pintype "passive"))
      (node (ref "D23") (pin "A") (pinfunction "A_A") (pintype "passive"))
      (node (ref "D24") (pin "A") (pinfunction "A_A") (pintype "passive"))
      (node (ref "D25") (pin "A") (pinfunction "A_A") (pintype "passive"))
      (node (ref "D26") (pin "A") (pinfunction "A_A") (pintype "passive"))
      (node (ref "D27") (pin "A") (pinfunction "A_A") (pintype "passive"))
      (node (ref "D28") (pin "A") (pinfunction "A_A") (pintype "passive"))
      (node (ref "D30") (pin "A") (pinfunction "A_A") (pintype "passive"))
      (node (ref "LED1") (pin "K") (pinfunction "C_K") (pintype "passive"))
      (node (ref "LED10") (pin "K") (pinfunction "C_K") (pintype "passive"))
      (node (ref "LED17") (pin "K") (pinfunction "C_K") (pintype "passive"))
      (node (ref "LED18") (pin "K") (pinfunction "C_K") (pintype "passive"))
      (node (ref "LED2") (pin "K") (pinfunction "C_K") (pintype "passive"))
      (node (ref "LED3") (pin "K") (pinfunction "C_K") (pintype "passive"))
      (node (ref "LED4") (pin "K") (pinfunction "C_K") (pintype "passive"))
      (node (ref "LED5") (pin "K") (pinfunction "C_K") (pintype "passive"))
      (node (ref "LED6") (pin "K") (pinfunction "C_K") (pintype "passive"))
      (node (ref "LED7") (pin "K") (pinfunction "C_K") (pintype "passive"))
      (node (ref "LED8") (pin "K") (pinfunction "C_K") (pintype "passive"))
      (node (ref "LED9") (pin "K") (pinfunction "C_K") (pintype "passive"))
      (node (ref "Q10") (pin "S") (pinfunction "S_S") (pintype "passive"))
      (node (ref "Q11") (pin "S") (pinfunction "S_S") (pintype "passive"))
      (node (ref "Q12") (pin "S") (pinfunction "S_S") (pintype "passive"))
      (node (ref "Q13") (pin "S") (pinfunction "S_S") (pintype "passive"))
      (node (ref "Q8") (pin "S") (pinfunction "S_S") (pintype "passive"))
      (node (ref "Q9") (pin "S") (pinfunction "S_S") (pintype "passive"))
      (node (ref "R38") (pin "2") (pinfunction "2_2") (pintype "passive"))
      (node (ref "R41") (pin "2") (pinfunction "2_2") (pintype "passive"))
      (node (ref "R44") (pin "2") (pinfunction "2_2") (pintype "passive"))
      (node (ref "R47") (pin "2") (pinfunction "2_2") (pintype "passive"))
      (node (ref "R52") (pin "1") (pinfunction "1_1") (pintype "passive"))
      (node (ref "R56") (pin "2") (pinfunction "2_2") (pintype "passive"))
      (node (ref "R60") (pin "2") (pinfunction "2_2") (pintype "passive"))
      (node (ref "R64") (pin "2") (pinfunction "2_2") (pintype "passive"))
      (node (ref "R68") (pin "2") (pinfunction "2_2") (pintype "passive"))
      (node (ref "R72") (pin "2") (pinfunction "2_2") (pintype "passive"))
      (node (ref "R76") (pin "2") (pinfunction "2_2") (pintype "passive"))
      (node (ref "R86") (pin "1") (pinfunction "1_1") (pintype "passive"))
      (node (ref "R90") (pin "1") (pinfunction "1_1") (pintype "passive"))
      (node (ref "R91") (pin "1") (pinfunction "1_1") (pintype "passive"))
      (node (ref "R92") (pin "1") (pinfunction "1_1") (pintype "passive"))
      (node (ref "R93") (pin "1") (pinfunction "1_1") (pintype "passive"))
      (node (ref "R94") (pin "1") (pinfunction "1_1") (pintype "passive"))
      (node (ref "R95") (pin "1") (pinfunction "1_1") (pintype "passive"))
      (node (ref "R96") (pin "1") (pinfunction "1_1") (pintype "passive"))
      (node (ref "U3") (pin "6") (pinfunction "C_6") (pintype "passive"))
      (node (ref "U3") (pin "8") (pinfunction "C_8") (pintype "passive"))
      (node (ref "U5") (pin "7") (pinfunction "VSS_7") (pintype "power_in"))
      (node (ref "X1") (pin "2") (pinfunction "S_2") (pintype "passive"))
      (node (ref "X1") (pin "4") (pinfunction "S_4") (pintype "passive"))
      (node (ref "X2") (pin "3") (pinfunction "S_3") (pintype "passive"))
      (node (ref "X2") (pin "6") (pinfunction "S_6") (pintype "passive"))
      (node (ref "X3") (pin "3") (pinfunction "S_3") (pintype "passive"))
      (node (ref "X3") (pin "6") (pinfunction "S_6") (pintype "passive"))
    )
    (net (code "16") (name "Net-(C4-Pad1)") (class "Default")
      (node (ref "C4") (pin "1") (pinfunction "1_1") (pintype "passive"))
      (node (ref "D5") (pin "C") (pinfunction "C_C") (pintype "passive"))
      (node (ref "D6") (pin "A") (pinfunction "A_A") (pintype "passive"))
    )
    (net (code "17") (name "Net-(C4-Pad2)") (class "Default")
      (node (ref "C4") (pin "2") (pinfunction "2_2") (pintype "passive"))
      (node (ref "R28") (pin "2") (pinfunction "2_2") (pintype "passive"))
    )
    (net (code "18") (name "Net-(C7-Pad1)") (class "Default")
      (node (ref "C7") (pin "1") (pinfunction "1_1") (pintype "passive"))
      (node (ref "D7") (pin "C") (pinfunction "C_C") (pintype "passive"))
      (node (ref "D8") (pin "A") (pinfunction "A_A") (pintype "passive"))
    )
    (net (code "19") (name "Net-(C7-Pad2)") (class "Default")
      (node (ref "C7") (pin "2") (pinfunction "2_2") (pintype "passive"))
      (node (ref "R32") (pin "2") (pinfunction "2_2") (pintype "passive"))
    )
    (net (code "20") (name "Net-(C9-Pad1)") (class "Default")
      (node (ref "C9") (pin "1") (pinfunction "1_1") (pintype "passive"))
      (node (ref "Q8") (pin "D") (pinfunction "D_D") (pintype "passive"))
      (node (ref "R53") (pin "2") (pinfunction "2_2") (pintype "passive"))
      (node (ref "R55") (pin "2") (pinfunction "2_2") (pintype "passive"))
      (node (ref "R77") (pin "1") (pinfunction "1_1") (pintype "passive"))
    )
    (net (code "21") (name "Net-(C9-Pad2)") (class "Default")
      (node (ref "C9") (pin "2") (pinfunction "2_2") (pintype "passive"))
      (node (ref "D23") (pin "C") (pinfunction "C_C") (pintype "passive"))
      (node (ref "Q8") (pin "G") (pinfunction "G_G") (pintype "passive"))
      (node (ref "R54") (pin "2") (pinfunction "2_2") (pintype "passive"))
      (node (ref "R56") (pin "1") (pinfunction "1_1") (pintype "passive"))
    )
    (net (code "22") (name "Net-(C10-Pad1)") (class "Default")
      (node (ref "C10") (pin "1") (pinfunction "1_1") (pintype "passive"))
      (node (ref "Q9") (pin "D") (pinfunction "D_D") (pintype "passive"))
      (node (ref "R57") (pin "2") (pinfunction "2_2") (pintype "passive"))
      (node (ref "R59") (pin "2") (pinfunction "2_2") (pintype "passive"))
      (node (ref "R78") (pin "1") (pinfunction "1_1") (pintype "passive"))
    )
    (net (code "23") (name "Net-(C10-Pad2)") (class "Default")
      (node (ref "C10") (pin "2") (pinfunction "2_2") (pintype "passive"))
      (node (ref "D24") (pin "C") (pinfunction "C_C") (pintype "passive"))
      (node (ref "Q9") (pin "G") (pinfunction "G_G") (pintype "passive"))
      (node (ref "R58") (pin "2") (pinfunction "2_2") (pintype "passive"))
      (node (ref "R60") (pin "1") (pinfunction "1_1") (pintype "passive"))
    )
    (net (code "24") (name "Net-(C11-Pad1)") (class "Default")
      (node (ref "C11") (pin "1") (pinfunction "1_1") (pintype "passive"))
      (node (ref "Q10") (pin "D") (pinfunction "D_D") (pintype "passive"))
      (node (ref "R61") (pin "2") (pinfunction "2_2") (pintype "passive"))
      (node (ref "R63") (pin "2") (pinfunction "2_2") (pintype "passive"))
      (node (ref "R79") (pin "1") (pinfunction "1_1") (pintype "passive"))
    )
    (net (code "25") (name "Net-(C11-Pad2)") (class "Default")
      (node (ref "C11") (pin "2") (pinfunction "2_2") (pintype "passive"))
      (node (ref "D25") (pin "C") (pinfunction "C_C") (pintype "passive"))
      (node (ref "Q10") (pin "G") (pinfunction "G_G") (pintype "passive"))
      (node (ref "R62") (pin "2") (pinfunction "2_2") (pintype "passive"))
      (node (ref "R64") (pin "1") (pinfunction "1_1") (pintype "passive"))
    )
    (net (code "26") (name "Net-(C12-Pad1)") (class "Default")
      (node (ref "C12") (pin "1") (pinfunction "1_1") (pintype "passive"))
      (node (ref "Q11") (pin "D") (pinfunction "D_D") (pintype "passive"))
      (node (ref "R65") (pin "2") (pinfunction "2_2") (pintype "passive"))
      (node (ref "R67") (pin "2") (pinfunction "2_2") (pintype "passive"))
      (node (ref "R80") (pin "1") (pinfunction "1_1") (pintype "passive"))
    )
    (net (code "27") (name "Net-(C12-Pad2)") (class "Default")
      (node (ref "C12") (pin "2") (pinfunction "2_2") (pintype "passive"))
      (node (ref "D26") (pin "C") (pinfunction "C_C") (pintype "passive"))
      (node (ref "Q11") (pin "G") (pinfunction "G_G") (pintype "passive"))
      (node (ref "R66") (pin "2") (pinfunction "2_2") (pintype "passive"))
      (node (ref "R68") (pin "1") (pinfunction "1_1") (pintype "passive"))
    )
    (net (code "28") (name "Net-(C13-Pad1)") (class "Default")
      (node (ref "C13") (pin "1") (pinfunction "1_1") (pintype "passive"))
      (node (ref "Q12") (pin "D") (pinfunction "D_D") (pintype "passive"))
      (node (ref "R69") (pin "2") (pinfunction "2_2") (pintype "passive"))
      (node (ref "R71") (pin "2") (pinfunction "2_2") (pintype "passive"))
      (node (ref "R81") (pin "1") (pinfunction "1_1") (pintype "passive"))
    )
    (net (code "29") (name "Net-(C13-Pad2)") (class "Default")
      (node (ref "C13") (pin "2") (pinfunction "2_2") (pintype "passive"))
      (node (ref "D27") (pin "C") (pinfunction "C_C") (pintype "passive"))
      (node (ref "Q12") (pin "G") (pinfunction "G_G") (pintype "passive"))
      (node (ref "R70") (pin "2") (pinfunction "2_2") (pintype "passive"))
      (node (ref "R72") (pin "1") (pinfunction "1_1") (pintype "passive"))
    )
    (net (code "30") (name "Net-(C14-Pad1)") (class "Default")
      (node (ref "C14") (pin "1") (pinfunction "1_1") (pintype "passive"))
      (node (ref "Q13") (pin "D") (pinfunction "D_D") (pintype "passive"))
      (node (ref "R73") (pin "2") (pinfunction "2_2") (pintype "passive"))
      (node (ref "R75") (pin "2") (pinfunction "2_2") (pintype "passive"))
      (node (ref "R82") (pin "1") (pinfunction "1_1") (pintype "passive"))
    )
    (net (code "31") (name "Net-(C14-Pad2)") (class "Default")
      (node (ref "C14") (pin "2") (pinfunction "2_2") (pintype "passive"))
      (node (ref "D28") (pin "C") (pinfunction "C_C") (pintype "passive"))
      (node (ref "Q13") (pin "G") (pinfunction "G_G") (pintype "passive"))
      (node (ref "R74") (pin "2") (pinfunction "2_2") (pintype "passive"))
      (node (ref "R76") (pin "1") (pinfunction "1_1") (pintype "passive"))
    )
    (net (code "32") (name "Net-(C20-Pad1)") (class "Default")
      (node (ref "C20") (pin "1") (pinfunction "1_1") (pintype "passive"))
      (node (ref "R85") (pin "2") (pinfunction "2_2") (pintype "passive"))
    )
    (net (code "33") (name "Net-(C20-Pad2)") (class "Default")
      (node (ref "C20") (pin "2") (pinfunction "2_2") (pintype "passive"))
      (node (ref "D29") (pin "A") (pinfunction "A_A") (pintype "passive"))
      (node (ref "D30") (pin "C") (pinfunction "C_C") (pintype "passive"))
    )
    (net (code "34") (name "Net-(IOXA-S)") (class "Default")
      (node (ref "IOX") (pin "1") (pinfunction "S_1") (pintype "passive"))
      (node (ref "PORTA") (pin "1") (pinfunction "S_1") (pintype "passive"))
    )
    (net (code "35") (name "Net-(IOXC-S)") (class "Default")
      (node (ref "IOX") (pin "2") (pinfunction "S_2") (pintype "passive"))
      (node (ref "PORTA") (pin "2") (pinfunction "S_2") (pintype "passive"))
    )
    (net (code "36") (name "Net-(IOXF-S)") (class "Default")
      (node (ref "IOX") (pin "5") (pinfunction "S_5") (pintype "passive"))
      (node (ref "R87") (pin "2") (pinfunction "2_2") (pintype "passive"))
    )
    (net (code "37") (name "Net-(IOXG-S)") (class "Default")
      (node (ref "IOX") (pin "6") (pinfunction "S_6") (pintype "passive"))
      (node (ref "R88") (pin "2") (pinfunction "2_2") (pintype "passive"))
    )
    (net (code "38") (name "Net-(IOXH-S)") (class "Default")
      (node (ref "IOX") (pin "7") (pinfunction "S_7") (pintype "passive"))
      (node (ref "R89") (pin "2") (pinfunction "2_2") (pintype "passive"))
    )
    (net (code "39") (name "Net-(LED1-PadA)") (class "Default")
      (node (ref "LED1") (pin "A") (pinfunction "A_A") (pintype "passive"))
      (node (ref "R11") (pin "2") (pinfunction "2_2") (pintype "passive"))
    )
    (net (code "40") (name "Net-(LED2-PadA)") (class "Default")
      (node (ref "LED2") (pin "A") (pinfunction "A_A") (pintype "passive"))
      (node (ref "R12") (pin "2") (pinfunction "2_2") (pintype "passive"))
    )
    (net (code "41") (name "Net-(LED3-PadA)") (class "Default")
      (node (ref "LED3") (pin "A") (pinfunction "A_A") (pintype "passive"))
      (node (ref "R13") (pin "2") (pinfunction "2_2") (pintype "passive"))
    )
    (net (code "42") (name "Net-(LED4-PadA)") (class "Default")
      (node (ref "LED4") (pin "A") (pinfunction "A_A") (pintype "passive"))
      (node (ref "R14") (pin "2") (pinfunction "2_2") (pintype "passive"))
    )
    (net (code "43") (name "Net-(LED5-PadA)") (class "Default")
      (node (ref "LED5") (pin "A") (pinfunction "A_A") (pintype "passive"))
      (node (ref "R15") (pin "2") (pinfunction "2_2") (pintype "passive"))
    )
    (net (code "44") (name "Net-(LED6-PadA)") (class "Default")
      (node (ref "LED6") (pin "A") (pinfunction "A_A") (pintype "passive"))
      (node (ref "R16") (pin "2") (pinfunction "2_2") (pintype "passive"))
    )
    (net (code "45") (name "Net-(LED7-PadA)") (class "Default")
      (node (ref "LED7") (pin "A") (pinfunction "A_A") (pintype "passive"))
      (node (ref "R17") (pin "2") (pinfunction "2_2") (pintype "passive"))
    )
    (net (code "46") (name "Net-(LED8-PadA)") (class "Default")
      (node (ref "LED8") (pin "A") (pinfunction "A_A") (pintype "passive"))
      (node (ref "R18") (pin "2") (pinfunction "2_2") (pintype "passive"))
    )
    (net (code "47") (name "Net-(LED9-PadA)") (class "Default")
      (node (ref "LED9") (pin "A") (pinfunction "A_A") (pintype "passive"))
      (node (ref "R21") (pin "1") (pinfunction "1_1") (pintype "passive"))
    )
    (net (code "48") (name "Net-(LED10-PadA)") (class "Default")
      (node (ref "LED10") (pin "A") (pinfunction "A_A") (pintype "passive"))
      (node (ref "R22") (pin "1") (pinfunction "1_1") (pintype "passive"))
    )
    (net (code "49") (name "Net-(LED11-C)") (class "Default")
      (node (ref "LED11") (pin "K") (pinfunction "C_K") (pintype "passive"))
      (node (ref "R77") (pin "2") (pinfunction "2_2") (pintype "passive"))
    )
    (net (code "50") (name "Net-(LED12-C)") (class "Default")
      (node (ref "LED12") (pin "K") (pinfunction "C_K") (pintype "passive"))
      (node (ref "R78") (pin "2") (pinfunction "2_2") (pintype "passive"))
    )
    (net (code "51") (name "Net-(LED13-C)") (class "Default")
      (node (ref "LED13") (pin "K") (pinfunction "C_K") (pintype "passive"))
      (node (ref "R79") (pin "2") (pinfunction "2_2") (pintype "passive"))
    )
    (net (code "52") (name "Net-(LED14-C)") (class "Default")
      (node (ref "LED14") (pin "K") (pinfunction "C_K") (pintype "passive"))
      (node (ref "R80") (pin "2") (pinfunction "2_2") (pintype "passive"))
    )
    (net (code "53") (name "Net-(LED15-C)") (class "Default")
      (node (ref "LED15") (pin "K") (pinfunction "C_K") (pintype "passive"))
      (node (ref "R81") (pin "2") (pinfunction "2_2") (pintype "passive"))
    )
    (net (code "54") (name "Net-(LED16-C)") (class "Default")
      (node (ref "LED16") (pin "K") (pinfunction "C_K") (pintype "passive"))
      (node (ref "R82") (pin "2") (pinfunction "2_2") (pintype "passive"))
    )
    (net (code "55") (name "Net-(LED17-PadA)") (class "Default")
      (node (ref "LED17") (pin "A") (pinfunction "A_A") (pintype "passive"))
      (node (ref "R83") (pin "1") (pinfunction "1_1") (pintype "passive"))
    )
    (net (code "56") (name "Net-(LED18-PadA)") (class "Default")
      (node (ref "LED18") (pin "A") (pinfunction "A_A") (pintype "passive"))
      (node (ref "R84") (pin "1") (pinfunction "1_1") (pintype "passive"))
    )
    (net (code "57") (name "Net-(PORTAF-S)") (class "Default")
      (node (ref "C5") (pin "2") (pinfunction "2_2") (pintype "passive"))
      (node (ref "D6") (pin "C") (pinfunction "C_C") (pintype "passive"))
      (node (ref "PORTA") (pin "5") (pinfunction "S_5") (pintype "passive"))
      (node (ref "R30") (pin "1") (pinfunction "1_1") (pintype "passive"))
    )
    (net (code "58") (name "Net-(PORTAG-S)") (class "Default")
      (node (ref "C6") (pin "2") (pinfunction "2_2") (pintype "passive"))
      (node (ref "D8") (pin "C") (pinfunction "C_C") (pintype "passive"))
      (node (ref "PORTA") (pin "6") (pinfunction "S_6") (pintype "passive"))
      (node (ref "R33") (pin "1") (pinfunction "1_1") (pintype "passive"))
    )
    (net (code "59") (name "Net-(PORTAH-S)") (class "Default")
      (node (ref "PORTA") (pin "7") (pinfunction "S_7") (pintype "passive"))
      (node (ref "R24") (pin "2") (pinfunction "2_2") (pintype "passive"))
    )
    (net (code "60") (name "Net-(PORTAI-S)") (class "Default")
      (node (ref "PORTA") (pin "8") (pinfunction "S_8") (pintype "passive"))
      (node (ref "R25") (pin "2") (pinfunction "2_2") (pintype "passive"))
    )
    (net (code "61") (name "Net-(PORTBA-S)") (class "Default")
      (node (ref "PORTB") (pin "1") (pinfunction "S_1") (pintype "passive"))
      (node (ref "U3") (pin "10") (pinfunction "COL_10") (pintype "passive"))
      (node (ref "U3") (pin "12") (pinfunction "COL_12") (pintype "passive"))
    )
    (net (code "62") (name "Net-(PORTBD-S)") (class "Default")
      (node (ref "PORTB") (pin "3") (pinfunction "S_3") (pintype "passive"))
      (node (ref "R9") (pin "1") (pinfunction "1_1") (pintype "passive"))
      (node (ref "U3") (pin "11") (pinfunction "EMIT_11") (pintype "passive"))
    )
    (net (code "63") (name "Net-(PORTBE-S)") (class "Default")
      (node (ref "PORTB") (pin "4") (pinfunction "S_4") (pintype "passive"))
      (node (ref "R10") (pin "1") (pinfunction "1_1") (pintype "passive"))
      (node (ref "U3") (pin "9") (pinfunction "EMIT_9") (pintype "passive"))
    )
    (net (code "64") (name "Net-(PORTBF-S)") (class "Default")
      (node (ref "PORTB") (pin "5") (pinfunction "S_5") (pintype "passive"))
      (node (ref "R23") (pin "2") (pinfunction "2_2") (pintype "passive"))
    )
    (net (code "65") (name "Net-(PORTBG-S)") (class "Default")
      (node (ref "PORTB") (pin "6") (pinfunction "S_6") (pintype "passive"))
      (node (ref "R89") (pin "1") (pinfunction "1_1") (pintype "passive"))
    )
    (net (code "66") (name "Net-(PORTBH-S)") (class "Default")
      (node (ref "PORTB") (pin "7") (pinfunction "S_7") (pintype "passive"))
      (node (ref "R4") (pin "2") (pinfunction "2_2") (pintype "passive"))
    )
    (net (code "67") (name "Net-(PORTBI-S)") (class "Default")
      (node (ref "PORTB") (pin "8") (pinfunction "S_8") (pintype "passive"))
      (node (ref "R3") (pin "2") (pinfunction "2_2") (pintype "passive"))
    )
    (net (code "68") (name "Net-(PORTDB-S)") (class "Default")
      (node (ref "PORTD") (pin "10") (pinfunction "S_10") (pintype "passive"))
      (node (ref "R5") (pin "2") (pinfunction "2_2") (pintype "passive"))
    )
    (net (code "69") (name "Net-(PORTDD-S)") (class "Default")
      (node (ref "PORTD") (pin "3") (pinfunction "S_3") (pintype "passive"))
      (node (ref "R1") (pin "2") (pinfunction "2_2") (pintype "passive"))
    )
    (net (code "70") (name "Net-(PORTDE-S)") (class "Default")
      (node (ref "PORTD") (pin "4") (pinfunction "S_4") (pintype "passive"))
      (node (ref "R2") (pin "2") (pinfunction "2_2") (pintype "passive"))
    )
    (net (code "71") (name "Net-(PORTDF-S)") (class "Default")
      (node (ref "PORTD") (pin "5") (pinfunction "S_5") (pintype "passive"))
      (node (ref "R8") (pin "2") (pinfunction "2_2") (pintype "passive"))
    )
    (net (code "72") (name "Net-(PORTDG-S)") (class "Default")
      (node (ref "PORTD") (pin "6") (pinfunction "S_6") (pintype "passive"))
      (node (ref "R7") (pin "2") (pinfunction "2_2") (pintype "passive"))
    )
    (net (code "73") (name "Net-(PORTDH-S)") (class "Default")
      (node (ref "PORTD") (pin "7") (pinfunction "S_7") (pintype "passive"))
      (node (ref "R6") (pin "2") (pinfunction "2_2") (pintype "passive"))
    )
    (net (code "74") (name "Net-(PORTDI-S)") (class "Default")
      (node (ref "PORTD") (pin "8") (pinfunction "S_8") (pintype "passive"))
      (node (ref "R87") (pin "1") (pinfunction "1_1") (pintype "passive"))
    )
    (net (code "75") (name "Net-(PORTDJ-S)") (class "Default")
      (node (ref "PORTD") (pin "9") (pinfunction "S_9") (pintype "passive"))
      (node (ref "R88") (pin "1") (pinfunction "1_1") (pintype "passive"))
    )
    (net (code "76") (name "Net-(Q1-B)") (class "Default")
      (node (ref "Q1") (pin "2") (pinfunction "B_2") (pintype "passive"))
      (node (ref "R34") (pin "1") (pinfunction "1_1") (pintype "passive"))
    )
    (net (code "77") (name "Net-(Q1-E)") (class "Default")
      (node (ref "D10") (pin "C") (pinfunction "C_C") (pintype "passive"))
      (node (ref "D9") (pin "A") (pinfunction "A_A") (pintype "passive"))
      (node (ref "Q1") (pin "1") (pinfunction "E_1") (pintype "passive"))
      (node (ref "R35") (pin "2") (pinfunction "2_2") (pintype "passive"))
    )
    (net (code "78") (name "Net-(Q2-B)") (class "Default")
      (node (ref "Q2") (pin "2") (pinfunction "B_2") (pintype "passive"))
      (node (ref "R36") (pin "1") (pinfunction "1_1") (pintype "passive"))
    )
    (net (code "79") (name "Net-(Q2-C)") (class "Default")
      (node (ref "D11") (pin "C") (pinfunction "C_C") (pintype "passive"))
      (node (ref "D12") (pin "A") (pinfunction "A_A") (pintype "passive"))
      (node (ref "Q2") (pin "3") (pinfunction "C_3") (pintype "passive"))
      (node (ref "R37") (pin "2") (pinfunction "2_2") (pintype "passive"))
      (node (ref "R38") (pin "1") (pinfunction "1_1") (pintype "passive"))
    )
    (net (code "80") (name "Net-(Q3-B)") (class "Default")
      (node (ref "Q3") (pin "2") (pinfunction "B_2") (pintype "passive"))
      (node (ref "R39") (pin "1") (pinfunction "1_1") (pintype "passive"))
    )
    (net (code "81") (name "Net-(Q3-C)") (class "Default")
      (node (ref "D13") (pin "C") (pinfunction "C_C") (pintype "passive"))
      (node (ref "D14") (pin "A") (pinfunction "A_A") (pintype "passive"))
      (node (ref "Q3") (pin "3") (pinfunction "C_3") (pintype "passive"))
      (node (ref "R40") (pin "2") (pinfunction "2_2") (pintype "passive"))
      (node (ref "R41") (pin "1") (pinfunction "1_1") (pintype "passive"))
    )
    (net (code "82") (name "Net-(Q4-B)") (class "Default")
      (node (ref "Q4") (pin "2") (pinfunction "B_2") (pintype "passive"))
      (node (ref "R42") (pin "1") (pinfunction "1_1") (pintype "passive"))
    )
    (net (code "83") (name "Net-(Q4-C)") (class "Default")
      (node (ref "D15") (pin "C") (pinfunction "C_C") (pintype "passive"))
      (node (ref "D16") (pin "A") (pinfunction "A_A") (pintype "passive"))
      (node (ref "Q4") (pin "3") (pinfunction "C_3") (pintype "passive"))
      (node (ref "R43") (pin "2") (pinfunction "2_2") (pintype "passive"))
      (node (ref "R44") (pin "1") (pinfunction "1_1") (pintype "passive"))
    )
    (net (code "84") (name "Net-(Q5-B)") (class "Default")
      (node (ref "Q5") (pin "2") (pinfunction "B_2") (pintype "passive"))
      (node (ref "R45") (pin "1") (pinfunction "1_1") (pintype "passive"))
    )
    (net (code "85") (name "Net-(Q5-C)") (class "Default")
      (node (ref "D17") (pin "C") (pinfunction "C_C") (pintype "passive"))
      (node (ref "D18") (pin "A") (pinfunction "A_A") (pintype "passive"))
      (node (ref "Q5") (pin "3") (pinfunction "C_3") (pintype "passive"))
      (node (ref "R46") (pin "2") (pinfunction "2_2") (pintype "passive"))
      (node (ref "R47") (pin "1") (pinfunction "1_1") (pintype "passive"))
    )
    (net (code "86") (name "Net-(Q6-B)") (class "Default")
      (node (ref "Q6") (pin "2") (pinfunction "B_2") (pintype "passive"))
      (node (ref "R48") (pin "1") (pinfunction "1_1") (pintype "passive"))
    )
    (net (code "87") (name "Net-(Q6-E)") (class "Default")
      (node (ref "D19") (pin "A") (pinfunction "A_A") (pintype "passive"))
      (node (ref "D20") (pin "C") (pinfunction "C_C") (pintype "passive"))
      (node (ref "Q6") (pin "1") (pinfunction "E_1") (pintype "passive"))
      (node (ref "R49") (pin "2") (pinfunction "2_2") (pintype "passive"))
    )
    (net (code "88") (name "Net-(Q7-B)") (class "Default")
      (node (ref "Q7") (pin "2") (pinfunction "B_2") (pintype "passive"))
      (node (ref "R50") (pin "1") (pinfunction "1_1") (pintype "passive"))
    )
    (net (code "89") (name "Net-(Q7-E)") (class "Default")
      (node (ref "D21") (pin "A") (pinfunction "A_A") (pintype "passive"))
      (node (ref "D22") (pin "C") (pinfunction "C_C") (pintype "passive"))
      (node (ref "Q7") (pin "1") (pinfunction "E_1") (pintype "passive"))
      (node (ref "R51") (pin "2") (pinfunction "2_2") (pintype "passive"))
    )
    (net (code "90") (name "Net-(R23-Pad1)") (class "Default")
      (node (ref "R23") (pin "1") (pinfunction "1_1") (pintype "passive"))
      (node (ref "SV1") (pin "3") (pinfunction "3_3") (pintype "passive"))
    )
    (net (code "91") (name "Net-(R24-Pad1)") (class "Default")
      (node (ref "R24") (pin "1") (pinfunction "1_1") (pintype "passive"))
      (node (ref "SV1") (pin "2") (pinfunction "2_2") (pintype "passive"))
    )
    (net (code "92") (name "Net-(R25-Pad1)") (class "Default")
      (node (ref "R25") (pin "1") (pinfunction "1_1") (pintype "passive"))
      (node (ref "SV1") (pin "1") (pinfunction "1_1") (pintype "passive"))
    )
    (net (code "93") (name "Net-(U1A-A)") (class "Default")
      (node (ref "R1") (pin "1") (pinfunction "1_1") (pintype "passive"))
      (node (ref "U1") (pin "1") (pinfunction "A_1") (pintype "passive"))
    )
    (net (code "94") (name "Net-(U1B-A)") (class "Default")
      (node (ref "R2") (pin "1") (pinfunction "1_1") (pintype "passive"))
      (node (ref "U1") (pin "3") (pinfunction "A_3") (pintype "passive"))
    )
    (net (code "95") (name "Net-(U1C-A)") (class "Default")
      (node (ref "R3") (pin "1") (pinfunction "1_1") (pintype "passive"))
      (node (ref "U1") (pin "5") (pinfunction "A_5") (pintype "passive"))
    )
    (net (code "96") (name "Net-(U1D-A)") (class "Default")
      (node (ref "R4") (pin "1") (pinfunction "1_1") (pintype "passive"))
      (node (ref "U1") (pin "7") (pinfunction "A_7") (pintype "passive"))
    )
    (net (code "97") (name "Net-(U2A-A)") (class "Default")
      (node (ref "R5") (pin "1") (pinfunction "1_1") (pintype "passive"))
      (node (ref "U2") (pin "1") (pinfunction "A_1") (pintype "passive"))
    )
    (net (code "98") (name "Net-(U2B-A)") (class "Default")
      (node (ref "R6") (pin "1") (pinfunction "1_1") (pintype "passive"))
      (node (ref "U2") (pin "3") (pinfunction "A_3") (pintype "passive"))
    )
    (net (code "99") (name "Net-(U2C-A)") (class "Default")
      (node (ref "R7") (pin "1") (pinfunction "1_1") (pintype "passive"))
      (node (ref "U2") (pin "5") (pinfunction "A_5") (pintype "passive"))
    )
    (net (code "100") (name "Net-(U2D-A)") (class "Default")
      (node (ref "R8") (pin "1") (pinfunction "1_1") (pintype "passive"))
      (node (ref "U2") (pin "7") (pinfunction "A_7") (pintype "passive"))
    )
    (net (code "101") (name "Net-(U3C-A)") (class "Default")
      (node (ref "R19") (pin "1") (pinfunction "1_1") (pintype "passive"))
      (node (ref "U3") (pin "5") (pinfunction "A_5") (pintype "passive"))
    )
    (net (code "102") (name "Net-(U3D-A)") (class "Default")
      (node (ref "R20") (pin "1") (pinfunction "1_1") (pintype "passive"))
      (node (ref "U3") (pin "7") (pinfunction "A_7") (pintype "passive"))
    )
    (net (code "103") (name "Net-(U4A-C)") (class "Default")
      (node (ref "D3") (pin "A") (pinfunction "A_A") (pintype "passive"))
      (node (ref "R26") (pin "2") (pinfunction "2_2") (pintype "passive"))
      (node (ref "U4") (pin "2") (pinfunction "C_2") (pintype "passive"))
    )
    (net (code "104") (name "Net-(U4A-OUT)") (class "Default")
      (node (ref "R28") (pin "1") (pinfunction "1_1") (pintype "passive"))
      (node (ref "R29") (pin "1") (pinfunction "1_1") (pintype "passive"))
      (node (ref "U4") (pin "7") (pinfunction "OUT_7") (pintype "passive"))
    )
    (net (code "105") (name "Net-(U4B-C)") (class "Default")
      (node (ref "D4") (pin "A") (pinfunction "A_A") (pintype "passive"))
      (node (ref "R27") (pin "2") (pinfunction "2_2") (pintype "passive"))
      (node (ref "U4") (pin "3") (pinfunction "C_3") (pintype "passive"))
    )
    (net (code "106") (name "Net-(U4B-OUT)") (class "Default")
      (node (ref "R31") (pin "1") (pinfunction "1_1") (pintype "passive"))
      (node (ref "R32") (pin "1") (pinfunction "1_1") (pintype "passive"))
      (node (ref "U4") (pin "6") (pinfunction "OUT_6") (pintype "passive"))
    )
    (net (code "107") (name "Net-(U5A-I0)") (class "Default")
      (node (ref "C8") (pin "2") (pinfunction "2_2") (pintype "passive"))
      (node (ref "D29") (pin "C") (pinfunction "C_C") (pintype "passive"))
      (node (ref "R52") (pin "2") (pinfunction "2_2") (pintype "passive"))
      (node (ref "U5") (pin "1") (pinfunction "I0_1") (pintype "input"))
      (node (ref "U5") (pin "12") (pinfunction "I0_12") (pintype "input"))
      (node (ref "U5") (pin "5") (pinfunction "I0_5") (pintype "input"))
      (node (ref "U5") (pin "8") (pinfunction "I0_8") (pintype "input"))
    )
    (net (code "108") (name "Net-(U5A-O)") (class "Default")
      (node (ref "R36") (pin "2") (pinfunction "2_2") (pintype "passive"))
      (node (ref "U5") (pin "3") (pinfunction "O_3") (pintype "output"))
    )
    (net (code "109") (name "Net-(U5B-O)") (class "Default")
      (node (ref "R39") (pin "2") (pinfunction "2_2") (pintype "passive"))
      (node (ref "U5") (pin "4") (pinfunction "O_4") (pintype "output"))
    )
    (net (code "110") (name "Net-(U5C-O)") (class "Default")
      (node (ref "R42") (pin "2") (pinfunction "2_2") (pintype "passive"))
      (node (ref "U5") (pin "10") (pinfunction "O_10") (pintype "output"))
    )
    (net (code "111") (name "Net-(U5D-O)") (class "Default")
      (node (ref "R45") (pin "2") (pinfunction "2_2") (pintype "passive"))
      (node (ref "U5") (pin "11") (pinfunction "O_11") (pintype "output"))
    )
    (net (code "112") (name "Net-(X1B-S)") (class "Default")
      (node (ref "R49") (pin "1") (pinfunction "1_1") (pintype "passive"))
      (node (ref "X1") (pin "10") (pinfunction "S_10") (pintype "passive"))
    )
    (net (code "113") (name "Net-(X1C-S)") (class "Default")
      (node (ref "R51") (pin "1") (pinfunction "1_1") (pintype "passive"))
      (node (ref "X1") (pin "11") (pinfunction "S_11") (pintype "passive"))
    )
    (net (code "114") (name "Net-(X1F-S)") (class "Default")
      (node (ref "R54") (pin "1") (pinfunction "1_1") (pintype "passive"))
      (node (ref "X1") (pin "14") (pinfunction "S_14") (pintype "passive"))
    )
    (net (code "115") (name "Net-(X1G-S)") (class "Default")
      (node (ref "R55") (pin "1") (pinfunction "1_1") (pintype "passive"))
      (node (ref "X1") (pin "15") (pinfunction "S_15") (pintype "passive"))
    )
    (net (code "116") (name "Net-(X1H-S)") (class "Default")
      (node (ref "R58") (pin "1") (pinfunction "1_1") (pintype "passive"))
      (node (ref "X1") (pin "16") (pinfunction "S_16") (pintype "passive"))
    )
    (net (code "117") (name "Net-(X1I-S)") (class "Default")
      (node (ref "R59") (pin "1") (pinfunction "1_1") (pintype "passive"))
      (node (ref "X1") (pin "17") (pinfunction "S_17") (pintype "passive"))
    )
    (net (code "118") (name "Net-(X1J-S)") (class "Default")
      (node (ref "R62") (pin "1") (pinfunction "1_1") (pintype "passive"))
      (node (ref "X1") (pin "18") (pinfunction "S_18") (pintype "passive"))
    )
    (net (code "119") (name "Net-(X1K-S)") (class "Default")
      (node (ref "R63") (pin "1") (pinfunction "1_1") (pintype "passive"))
      (node (ref "X1") (pin "19") (pinfunction "S_19") (pintype "passive"))
    )
    (net (code "120") (name "Net-(X1M-S)") (class "Default")
      (node (ref "R66") (pin "1") (pinfunction "1_1") (pintype "passive"))
      (node (ref "X1") (pin "20") (pinfunction "S_20") (pintype "passive"))
    )
    (net (code "121") (name "Net-(X1N-S)") (class "Default")
      (node (ref "R67") (pin "1") (pinfunction "1_1") (pintype "passive"))
      (node (ref "X1") (pin "21") (pinfunction "S_21") (pintype "passive"))
    )
    (net (code "122") (name "Net-(X1O-S)") (class "Default")
      (node (ref "R70") (pin "1") (pinfunction "1_1") (pintype "passive"))
      (node (ref "X1") (pin "22") (pinfunction "S_22") (pintype "passive"))
    )
    (net (code "123") (name "Net-(X1P-S)") (class "Default")
      (node (ref "R71") (pin "1") (pinfunction "1_1") (pintype "passive"))
      (node (ref "X1") (pin "23") (pinfunction "S_23") (pintype "passive"))
    )
    (net (code "124") (name "Net-(X1Q-S)") (class "Default")
      (node (ref "R74") (pin "1") (pinfunction "1_1") (pintype "passive"))
      (node (ref "X1") (pin "24") (pinfunction "S_24") (pintype "passive"))
    )
    (net (code "125") (name "Net-(X1R-S)") (class "Default")
      (node (ref "R75") (pin "1") (pinfunction "1_1") (pintype "passive"))
      (node (ref "X1") (pin "25") (pinfunction "S_25") (pintype "passive"))
    )
    (net (code "126") (name "Net-(X1V-S)") (class "Default")
      (node (ref "R35") (pin "1") (pinfunction "1_1") (pintype "passive"))
      (node (ref "X1") (pin "5") (pinfunction "S_5") (pintype "passive"))
    )
    (net (code "127") (name "Net-(X1W-S)") (class "Default")
      (node (ref "R37") (pin "1") (pinfunction "1_1") (pintype "passive"))
      (node (ref "X1") (pin "6") (pinfunction "S_6") (pintype "passive"))
    )
    (net (code "128") (name "Net-(X1X-S)") (class "Default")
      (node (ref "R40") (pin "1") (pinfunction "1_1") (pintype "passive"))
      (node (ref "X1") (pin "7") (pinfunction "S_7") (pintype "passive"))
    )
    (net (code "129") (name "Net-(X1Y-S)") (class "Default")
      (node (ref "R43") (pin "1") (pinfunction "1_1") (pintype "passive"))
      (node (ref "X1") (pin "8") (pinfunction "S_8") (pintype "passive"))
    )
    (net (code "130") (name "Net-(X1Z-S)") (class "Default")
      (node (ref "R46") (pin "1") (pinfunction "1_1") (pintype "passive"))
      (node (ref "X1") (pin "9") (pinfunction "S_9") (pintype "passive"))
    )
    (net (code "131") (name "Net-(X2D-S)") (class "Default")
      (node (ref "R26") (pin "1") (pinfunction "1_1") (pintype "passive"))
      (node (ref "X2") (pin "4") (pinfunction "S_4") (pintype "passive"))
    )
    (net (code "132") (name "Net-(X3D-S)") (class "Default")
      (node (ref "R27") (pin "1") (pinfunction "1_1") (pintype "passive"))
      (node (ref "X3") (pin "4") (pinfunction "S_4") (pintype "passive"))
    )
    (net (code "133") (name "unconnected-(IOXB-S-Pad10)") (class "Default")
      (node (ref "IOX") (pin "10") (pinfunction "S_10") (pintype "passive"))
    )
    (net (code "134") (name "unconnected-(IOXI-S-Pad8)") (class "Default")
      (node (ref "IOX") (pin "8") (pinfunction "S_8") (pintype "passive"))
    )
    (net (code "135") (name "unconnected-(IOXJ-S-Pad9)") (class "Default")
      (node (ref "IOX") (pin "9") (pinfunction "S_9") (pintype "passive"))
    )
    (net (code "136") (name "unconnected-(PORTAB-S-Pad10)") (class "Default")
      (node (ref "PORTA") (pin "10") (pinfunction "S_10") (pintype "passive"))
    )
    (net (code "137") (name "unconnected-(PORTAD-S-Pad3)") (class "Default")
      (node (ref "PORTA") (pin "3") (pinfunction "S_3") (pintype "passive"))
    )
    (net (code "138") (name "unconnected-(PORTAE-S-Pad4)") (class "Default")
      (node (ref "PORTA") (pin "4") (pinfunction "S_4") (pintype "passive"))
    )
    (net (code "139") (name "unconnected-(PORTAJ-S-Pad9)") (class "Default")
      (node (ref "PORTA") (pin "9") (pinfunction "S_9") (pintype "passive"))
    )
    (net (code "140") (name "unconnected-(PORTBB-S-Pad10)") (class "Default")
      (node (ref "PORTB") (pin "10") (pinfunction "S_10") (pintype "passive"))
    )
    (net (code "141") (name "unconnected-(PORTBJ-S-Pad9)") (class "Default")
      (node (ref "PORTB") (pin "9") (pinfunction "S_9") (pintype "passive"))
    )
    (net (code "142") (name "unconnected-(U3A-A-Pad1)") (class "Default")
      (node (ref "U3") (pin "1") (pinfunction "A_1") (pintype "passive"))
    )
    (net (code "143") (name "unconnected-(U3A-C-Pad2)") (class "Default")
      (node (ref "U3") (pin "2") (pinfunction "C_2") (pintype "passive"))
    )
    (net (code "144") (name "unconnected-(U3A-COL-Pad16)") (class "Default")
      (node (ref "U3") (pin "16") (pinfunction "COL_16") (pintype "passive"))
    )
    (net (code "145") (name "unconnected-(U3A-EMIT-Pad15)") (class "Default")
      (node (ref "U3") (pin "15") (pinfunction "EMIT_15") (pintype "passive"))
    )
    (net (code "146") (name "unconnected-(U3B-A-Pad3)") (class "Default")
      (node (ref "U3") (pin "3") (pinfunction "A_3") (pintype "passive"))
    )
    (net (code "147") (name "unconnected-(U3B-C-Pad4)") (class "Default")
      (node (ref "U3") (pin "4") (pinfunction "C_4") (pintype "passive"))
    )
    (net (code "148") (name "unconnected-(U3B-COL-Pad14)") (class "Default")
      (node (ref "U3") (pin "14") (pinfunction "COL_14") (pintype "passive"))
    )
    (net (code "149") (name "unconnected-(U3B-EMIT-Pad13)") (class "Default")
      (node (ref "U3") (pin "13") (pinfunction "EMIT_13") (pintype "passive"))
    )
    (net (code "150") (name "unconnected-(X1S-S-Pad26)") (class "Default")
      (node (ref "X1") (pin "26") (pinfunction "S_26") (pintype "passive"))
    )
    (net (code "151") (name "unconnected-(X2B-S-Pad2)") (class "Default")
      (node (ref "X2") (pin "2") (pinfunction "S_2") (pintype "passive"))
    )
    (net (code "152") (name "unconnected-(X2E-S-Pad5)") (class "Default")
      (node (ref "X2") (pin "5") (pinfunction "S_5") (pintype "passive"))
    )
    (net (code "153") (name "unconnected-(X3B-S-Pad2)") (class "Default")
      (node (ref "X3") (pin "2") (pinfunction "S_2") (pintype "passive"))
    )
    (net (code "154") (name "unconnected-(X3E-S-Pad5)") (class "Default")
      (node (ref "X3") (pin "5") (pinfunction "S_5") (pintype "passive"))
    )
  )
)
